# sc300_microstep_piano.net
KiCad netlist of a schematic drawn in EAGLE
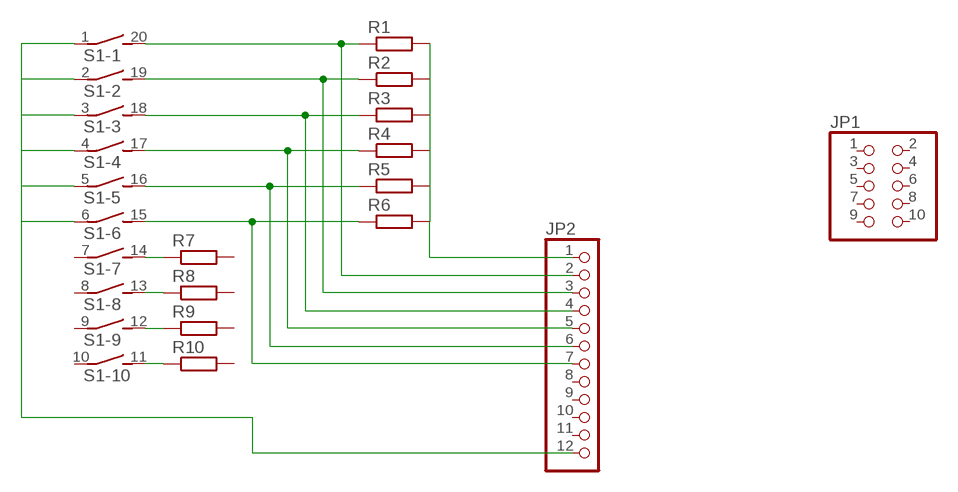
[diagram p0: schematic, sheet 1]
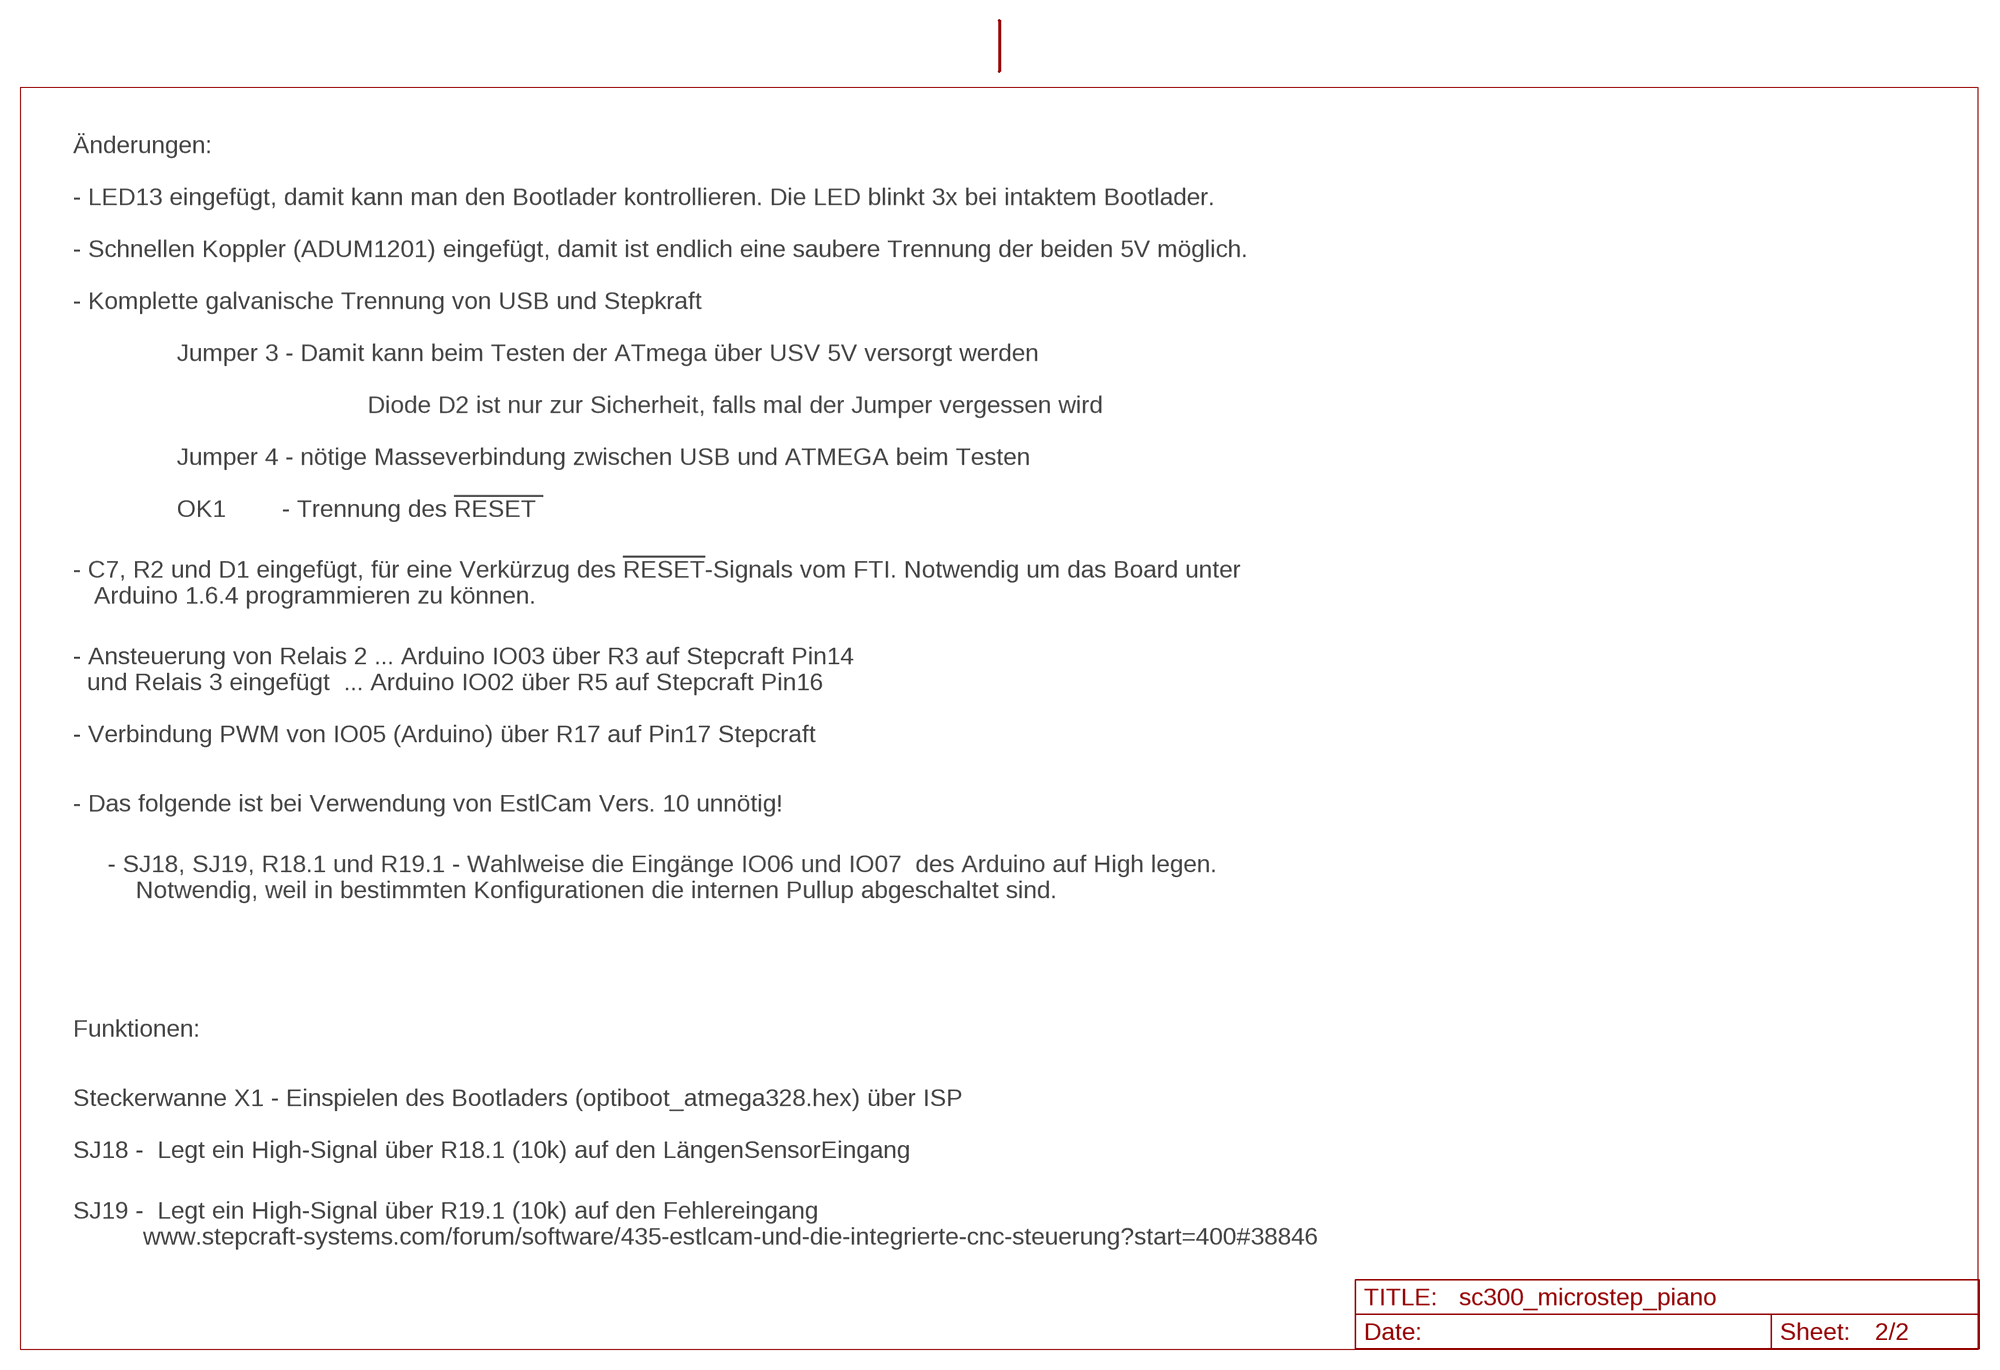
[diagram p1: schematic, sheet 2]

(export (version "E")
  (design (tool "Eeschema 10.0.6"))
  (components
    (comp (ref "JP1")
      (value "PINHD-2X5")
      (footprint "eagle-import:2X05")
      (libsource (lib "eagle-import") (part "PINHD-2X5"))
    )
    (comp (ref "JP2")
      (value "PINHD-1X12")
      (footprint "eagle-import:1X12")
      (libsource (lib "eagle-import") (part "PINHD-1X12"))
    )
    (comp (ref "R1")
      (value "R-EU_0603")
      (footprint "eagle-import:R0603")
      (libsource (lib "eagle-import") (part "R-EU_0603"))
    )
    (comp (ref "R2")
      (value "R-EU_0603")
      (footprint "eagle-import:R0603")
      (libsource (lib "eagle-import") (part "R-EU_0603"))
    )
    (comp (ref "R3")
      (value "R-EU_0603")
      (footprint "eagle-import:R0603")
      (libsource (lib "eagle-import") (part "R-EU_0603"))
    )
    (comp (ref "R4")
      (value "R-EU_0603")
      (footprint "eagle-import:R0603")
      (libsource (lib "eagle-import") (part "R-EU_0603"))
    )
    (comp (ref "R5")
      (value "R-EU_0603")
      (footprint "eagle-import:R0603")
      (libsource (lib "eagle-import") (part "R-EU_0603"))
    )
    (comp (ref "R6")
      (value "R-EU_0603")
      (footprint "eagle-import:R0603")
      (libsource (lib "eagle-import") (part "R-EU_0603"))
    )
    (comp (ref "R7")
      (value "R-EU_0603")
      (footprint "eagle-import:R0603")
      (libsource (lib "eagle-import") (part "R-EU_0603"))
    )
    (comp (ref "R8")
      (value "R-EU_0603")
      (footprint "eagle-import:R0603")
      (libsource (lib "eagle-import") (part "R-EU_0603"))
    )
    (comp (ref "R9")
      (value "R-EU_0603")
      (footprint "eagle-import:R0603")
      (libsource (lib "eagle-import") (part "R-EU_0603"))
    )
    (comp (ref "R10")
      (value "R-EU_0603")
      (footprint "eagle-import:R0603")
      (libsource (lib "eagle-import") (part "R-EU_0603"))
    )
    (comp (ref "S1")
      (value "DIP10SB")
      (footprint "eagle-import:DIP10SB")
      (libsource (lib "eagle-import") (part "DIP10SB"))
    )
  )
  (nets
    (net (code "1") (name "Net-(JP2-Pad1)") (class "Default")
      (node (ref "JP2") (pin "1") (pinfunction "1_1") (pintype "passive"))
      (node (ref "R1") (pin "2") (pinfunction "2_2") (pintype "passive"))
      (node (ref "R2") (pin "2") (pinfunction "2_2") (pintype "passive"))
      (node (ref "R3") (pin "2") (pinfunction "2_2") (pintype "passive"))
      (node (ref "R4") (pin "2") (pinfunction "2_2") (pintype "passive"))
      (node (ref "R5") (pin "2") (pinfunction "2_2") (pintype "passive"))
      (node (ref "R6") (pin "2") (pinfunction "2_2") (pintype "passive"))
    )
    (net (code "2") (name "Net-(S1A-2)") (class "Default")
      (node (ref "JP2") (pin "2") (pinfunction "2_2") (pintype "passive"))
      (node (ref "R1") (pin "1") (pinfunction "1_1") (pintype "passive"))
      (node (ref "S1") (pin "20") (pinfunction "2_20") (pintype "passive"))
    )
    (net (code "3") (name "Net-(S1B-2)") (class "Default")
      (node (ref "R10") (pin "1") (pinfunction "1_1") (pintype "passive"))
      (node (ref "S1") (pin "11") (pinfunction "2_11") (pintype "passive"))
    )
    (net (code "4") (name "Net-(S1C-1)") (class "Default")
      (node (ref "JP2") (pin "12") (pinfunction "12_12") (pintype "passive"))
      (node (ref "S1") (pin "1") (pinfunction "1_1") (pintype "passive"))
      (node (ref "S1") (pin "2") (pinfunction "1_2") (pintype "passive"))
      (node (ref "S1") (pin "3") (pinfunction "1_3") (pintype "passive"))
      (node (ref "S1") (pin "4") (pinfunction "1_4") (pintype "passive"))
      (node (ref "S1") (pin "5") (pinfunction "1_5") (pintype "passive"))
      (node (ref "S1") (pin "6") (pinfunction "1_6") (pintype "passive"))
    )
    (net (code "5") (name "Net-(S1C-2)") (class "Default")
      (node (ref "JP2") (pin "3") (pinfunction "3_3") (pintype "passive"))
      (node (ref "R2") (pin "1") (pinfunction "1_1") (pintype "passive"))
      (node (ref "S1") (pin "19") (pinfunction "2_19") (pintype "passive"))
    )
    (net (code "6") (name "Net-(S1D-2)") (class "Default")
      (node (ref "JP2") (pin "4") (pinfunction "4_4") (pintype "passive"))
      (node (ref "R3") (pin "1") (pinfunction "1_1") (pintype "passive"))
      (node (ref "S1") (pin "18") (pinfunction "2_18") (pintype "passive"))
    )
    (net (code "7") (name "Net-(S1E-2)") (class "Default")
      (node (ref "JP2") (pin "5") (pinfunction "5_5") (pintype "passive"))
      (node (ref "R4") (pin "1") (pinfunction "1_1") (pintype "passive"))
      (node (ref "S1") (pin "17") (pinfunction "2_17") (pintype "passive"))
    )
    (net (code "8") (name "Net-(S1F-2)") (class "Default")
      (node (ref "JP2") (pin "6") (pinfunction "6_6") (pintype "passive"))
      (node (ref "R5") (pin "1") (pinfunction "1_1") (pintype "passive"))
      (node (ref "S1") (pin "16") (pinfunction "2_16") (pintype "passive"))
    )
    (net (code "9") (name "Net-(S1G-2)") (class "Default")
      (node (ref "JP2") (pin "7") (pinfunction "7_7") (pintype "passive"))
      (node (ref "R6") (pin "1") (pinfunction "1_1") (pintype "passive"))
      (node (ref "S1") (pin "15") (pinfunction "2_15") (pintype "passive"))
    )
    (net (code "10") (name "Net-(S1H-2)") (class "Default")
      (node (ref "R7") (pin "1") (pinfunction "1_1") (pintype "passive"))
      (node (ref "S1") (pin "14") (pinfunction "2_14") (pintype "passive"))
    )
    (net (code "11") (name "Net-(S1I-2)") (class "Default")
      (node (ref "R8") (pin "1") (pinfunction "1_1") (pintype "passive"))
      (node (ref "S1") (pin "13") (pinfunction "2_13") (pintype "passive"))
    )
    (net (code "12") (name "Net-(S1J-2)") (class "Default")
      (node (ref "R9") (pin "1") (pinfunction "1_1") (pintype "passive"))
      (node (ref "S1") (pin "12") (pinfunction "2_12") (pintype "passive"))
    )
    (net (code "13") (name "unconnected-(JP1-Pad1)") (class "Default")
      (node (ref "JP1") (pin "1") (pinfunction "1_1") (pintype "passive"))
    )
    (net (code "14") (name "unconnected-(JP1-Pad2)") (class "Default")
      (node (ref "JP1") (pin "2") (pinfunction "2_2") (pintype "passive"))
    )
    (net (code "15") (name "unconnected-(JP1-Pad3)") (class "Default")
      (node (ref "JP1") (pin "3") (pinfunction "3_3") (pintype "passive"))
    )
    (net (code "16") (name "unconnected-(JP1-Pad4)") (class "Default")
      (node (ref "JP1") (pin "4") (pinfunction "4_4") (pintype "passive"))
    )
    (net (code "17") (name "unconnected-(JP1-Pad5)") (class "Default")
      (node (ref "JP1") (pin "5") (pinfunction "5_5") (pintype "passive"))
    )
    (net (code "18") (name "unconnected-(JP1-Pad6)") (class "Default")
      (node (ref "JP1") (pin "6") (pinfunction "6_6") (pintype "passive"))
    )
    (net (code "19") (name "unconnected-(JP1-Pad7)") (class "Default")
      (node (ref "JP1") (pin "7") (pinfunction "7_7") (pintype "passive"))
    )
    (net (code "20") (name "unconnected-(JP1-Pad8)") (class "Default")
      (node (ref "JP1") (pin "8") (pinfunction "8_8") (pintype "passive"))
    )
    (net (code "21") (name "unconnected-(JP1-Pad9)") (class "Default")
      (node (ref "JP1") (pin "9") (pinfunction "9_9") (pintype "passive"))
    )
    (net (code "22") (name "unconnected-(JP1-Pad10)") (class "Default")
      (node (ref "JP1") (pin "10") (pinfunction "10_10") (pintype "passive"))
    )
    (net (code "23") (name "unconnected-(JP2-Pad8)") (class "Default")
      (node (ref "JP2") (pin "8") (pinfunction "8_8") (pintype "passive"))
    )
    (net (code "24") (name "unconnected-(JP2-Pad9)") (class "Default")
      (node (ref "JP2") (pin "9") (pinfunction "9_9") (pintype "passive"))
    )
    (net (code "25") (name "unconnected-(JP2-Pad10)") (class "Default")
      (node (ref "JP2") (pin "10") (pinfunction "10_10") (pintype "passive"))
    )
    (net (code "26") (name "unconnected-(JP2-Pad11)") (class "Default")
      (node (ref "JP2") (pin "11") (pinfunction "11_11") (pintype "passive"))
    )
    (net (code "27") (name "unconnected-(R7-Pad2)") (class "Default")
      (node (ref "R7") (pin "2") (pinfunction "2_2") (pintype "passive"))
    )
    (net (code "28") (name "unconnected-(R8-Pad2)") (class "Default")
      (node (ref "R8") (pin "2") (pinfunction "2_2") (pintype "passive"))
    )
    (net (code "29") (name "unconnected-(R9-Pad2)") (class "Default")
      (node (ref "R9") (pin "2") (pinfunction "2_2") (pintype "passive"))
    )
    (net (code "30") (name "unconnected-(R10-Pad2)") (class "Default")
      (node (ref "R10") (pin "2") (pinfunction "2_2") (pintype "passive"))
    )
    (net (code "31") (name "unconnected-(S1B-1-Pad10)") (class "Default")
      (node (ref "S1") (pin "10") (pinfunction "1_10") (pintype "passive"))
    )
    (net (code "32") (name "unconnected-(S1H-1-Pad7)") (class "Default")
      (node (ref "S1") (pin "7") (pinfunction "1_7") (pintype "passive"))
    )
    (net (code "33") (name "unconnected-(S1I-1-Pad8)") (class "Default")
      (node (ref "S1") (pin "8") (pinfunction "1_8") (pintype "passive"))
    )
    (net (code "34") (name "unconnected-(S1J-1-Pad9)") (class "Default")
      (node (ref "S1") (pin "9") (pinfunction "1_9") (pintype "passive"))
    )
  )
)
